# test.net
KiCad netlist of a schematic drawn in EAGLE
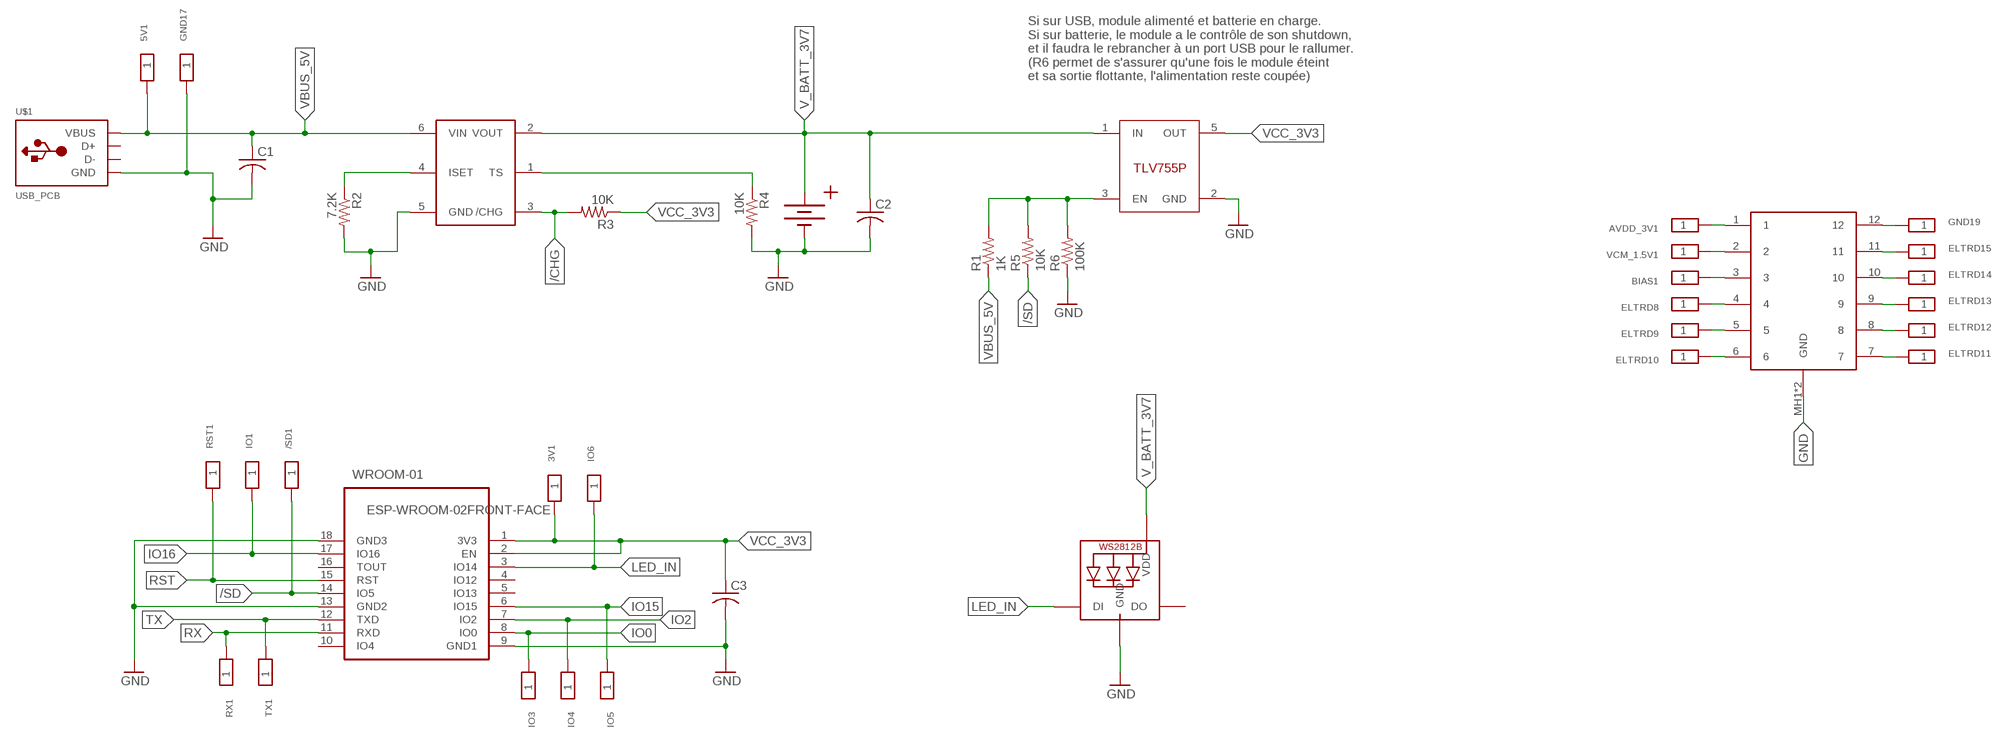
[diagram p0: schematic, sheet 1]

(export (version "E")
  (design (tool "Eeschema 10.0.6"))
  (components
    (comp (ref "/SD1")
      (value "TESTPAD_PROG")
      (footprint "eagle-import:TP1.5MM")
      (libsource (lib "eagle-import") (part "monoblink_wifi_TESTPAD_PROG"))
    )
    (comp (ref "3V1")
      (value "TESTPAD_PROG")
      (footprint "eagle-import:TP1.5MM")
      (libsource (lib "eagle-import") (part "monoblink_wifi_TESTPAD_PROG"))
    )
    (comp (ref "5V1")
      (value "TESTPAD_PROG")
      (footprint "eagle-import:TP1.5MM")
      (libsource (lib "eagle-import") (part "monoblink_wifi_TESTPAD_PROG"))
    )
    (comp (ref "AVDD_3V1")
      (value "TESTPAD_PROG")
      (footprint "eagle-import:TP1.5MM")
      (libsource (lib "eagle-import") (part "TESTPAD_PROG"))
    )
    (comp (ref "BIAS1")
      (value "TESTPAD_PROG")
      (footprint "eagle-import:TP1.5MM")
      (libsource (lib "eagle-import") (part "TESTPAD_PROG"))
    )
    (comp (ref "C1")
      (value "C-USC0603")
      (footprint "eagle-import:C0603")
      (libsource (lib "eagle-import") (part "C-USC0603"))
    )
    (comp (ref "C2")
      (value "C-USC0603")
      (footprint "eagle-import:C0603")
      (libsource (lib "eagle-import") (part "C-USC0603"))
    )
    (comp (ref "C3")
      (value "C-USC0603")
      (footprint "eagle-import:C0603")
      (libsource (lib "eagle-import") (part "C-USC0603"))
    )
    (comp (ref "CHG1")
      (value "BQ21040")
      (footprint "eagle-import:SOT23-6")
      (libsource (lib "eagle-import") (part "BQ21040"))
    )
    (comp (ref "CONN1")
      (value "505110-1292")
      (footprint "eagle-import:505110-1292")
      (libsource (lib "eagle-import") (part "505110-1292"))
    )
    (comp (ref "ELTRD8")
      (value "TESTPAD_PROG")
      (footprint "eagle-import:TP1.5MM")
      (libsource (lib "eagle-import") (part "TESTPAD_PROG"))
    )
    (comp (ref "ELTRD9")
      (value "TESTPAD_PROG")
      (footprint "eagle-import:TP1.5MM")
      (libsource (lib "eagle-import") (part "TESTPAD_PROG"))
    )
    (comp (ref "ELTRD10")
      (value "TESTPAD_PROG")
      (footprint "eagle-import:TP1.5MM")
      (libsource (lib "eagle-import") (part "TESTPAD_PROG"))
    )
    (comp (ref "ELTRD11")
      (value "TESTPAD_PROG")
      (footprint "eagle-import:TP1.5MM")
      (libsource (lib "eagle-import") (part "TESTPAD_PROG"))
    )
    (comp (ref "ELTRD12")
      (value "TESTPAD_PROG")
      (footprint "eagle-import:TP1.5MM")
      (libsource (lib "eagle-import") (part "TESTPAD_PROG"))
    )
    (comp (ref "ELTRD13")
      (value "TESTPAD_PROG")
      (footprint "eagle-import:TP1.5MM")
      (libsource (lib "eagle-import") (part "TESTPAD_PROG"))
    )
    (comp (ref "ELTRD14")
      (value "TESTPAD_PROG")
      (footprint "eagle-import:TP1.5MM")
      (libsource (lib "eagle-import") (part "TESTPAD_PROG"))
    )
    (comp (ref "ELTRD15")
      (value "TESTPAD_PROG")
      (footprint "eagle-import:TP1.5MM")
      (libsource (lib "eagle-import") (part "TESTPAD_PROG"))
    )
    (comp (ref "GND17")
      (value "TESTPAD_PROG")
      (footprint "eagle-import:TP1.5MM")
      (libsource (lib "eagle-import") (part "monoblink_wifi_TESTPAD_PROG"))
    )
    (comp (ref "GND19")
      (value "TESTPAD_PROG")
      (footprint "eagle-import:TP1.5MM")
      (libsource (lib "eagle-import") (part "TESTPAD_PROG"))
    )
    (comp (ref "IO1")
      (value "TESTPAD_PROG")
      (footprint "eagle-import:TP1.5MM")
      (libsource (lib "eagle-import") (part "monoblink_wifi_TESTPAD_PROG"))
    )
    (comp (ref "IO3")
      (value "TESTPAD_PROG")
      (footprint "eagle-import:TP1.5MM")
      (libsource (lib "eagle-import") (part "monoblink_wifi_TESTPAD_PROG"))
    )
    (comp (ref "IO4")
      (value "TESTPAD_PROG")
      (footprint "eagle-import:TP1.5MM")
      (libsource (lib "eagle-import") (part "monoblink_wifi_TESTPAD_PROG"))
    )
    (comp (ref "IO5")
      (value "TESTPAD_PROG")
      (footprint "eagle-import:TP1.5MM")
      (libsource (lib "eagle-import") (part "monoblink_wifi_TESTPAD_PROG"))
    )
    (comp (ref "IO6")
      (value "TESTPAD_PROG")
      (footprint "eagle-import:TP1.5MM")
      (libsource (lib "eagle-import") (part "monoblink_wifi_TESTPAD_PROG"))
    )
    (comp (ref "LDO1")
      (value "TLV755P")
      (footprint "eagle-import:SOT23-5")
      (libsource (lib "eagle-import") (part "TLV755P"))
    )
    (comp (ref "LED1")
      (value "WS2812B5050")
      (footprint "eagle-import:WS2812B")
      (libsource (lib "eagle-import") (part "WS2812B5050"))
    )
    (comp (ref "R1")
      (value "1K")
      (footprint "eagle-import:R0603")
      (libsource (lib "eagle-import") (part "R-US_R0603"))
    )
    (comp (ref "R2")
      (value "7.2K")
      (footprint "eagle-import:R0603")
      (libsource (lib "eagle-import") (part "R-US_R0603"))
    )
    (comp (ref "R3")
      (value "10K")
      (footprint "eagle-import:R0603")
      (libsource (lib "eagle-import") (part "R-US_R0603"))
    )
    (comp (ref "R4")
      (value "10K")
      (footprint "eagle-import:R0603")
      (libsource (lib "eagle-import") (part "R-US_R0603"))
    )
    (comp (ref "R5")
      (value "10K")
      (footprint "eagle-import:R0603")
      (libsource (lib "eagle-import") (part "R-US_R0603"))
    )
    (comp (ref "R6")
      (value "100K")
      (footprint "eagle-import:R0603")
      (libsource (lib "eagle-import") (part "R-US_R0603"))
    )
    (comp (ref "RST1")
      (value "TESTPAD_PROG")
      (footprint "eagle-import:TP1.5MM")
      (libsource (lib "eagle-import") (part "monoblink_wifi_TESTPAD_PROG"))
    )
    (comp (ref "RX1")
      (value "TESTPAD_PROG")
      (footprint "eagle-import:TP1.5MM")
      (libsource (lib "eagle-import") (part "monoblink_wifi_TESTPAD_PROG"))
    )
    (comp (ref "TX1")
      (value "TESTPAD_PROG")
      (footprint "eagle-import:TP1.5MM")
      (libsource (lib "eagle-import") (part "monoblink_wifi_TESTPAD_PROG"))
    )
    (comp (ref "U$1")
      (value "USB_PCB")
      (footprint "eagle-import:USB_PADS")
      (libsource (lib "eagle-import") (part "USB_PCB"))
    )
    (comp (ref "U$3")
      (value "BATT")
      (footprint "eagle-import:BATT_CON")
      (libsource (lib "eagle-import") (part "BATT"))
    )
    (comp (ref "VCM_1.5V1")
      (value "TESTPAD_PROG")
      (footprint "eagle-import:TP1.5MM")
      (libsource (lib "eagle-import") (part "TESTPAD_PROG"))
    )
    (comp (ref "WROOM-01")
      (value "ESP-WROOM-02FRONT-FACE")
      (footprint "eagle-import:FRONT-FACE")
      (libsource (lib "eagle-import") (part "ESP-WROOM-02FRONT-FACE"))
    )
  )
  (nets
    (net (code "1") (name "GND") (class "Default")
      (node (ref "C1") (pin "2") (pinfunction "2_2") (pintype "passive"))
      (node (ref "C2") (pin "2") (pinfunction "2_2") (pintype "passive"))
      (node (ref "C3") (pin "2") (pinfunction "2_2") (pintype "passive"))
      (node (ref "CHG1") (pin "5") (pinfunction "GND_5") (pintype "bidirectional"))
      (node (ref "CONN1") (pin "MH1") (pinfunction "GND_MH1") (pintype "bidirectional"))
      (node (ref "CONN1") (pin "MH2") (pinfunction "GND_MH2") (pintype "bidirectional"))
      (node (ref "GND17") (pin "1") (pinfunction "1_1") (pintype "bidirectional"))
      (node (ref "LDO1") (pin "2") (pinfunction "GND_2") (pintype "bidirectional"))
      (node (ref "LED1") (pin "3-GND") (pinfunction "GND_3-GND") (pintype "power_in"))
      (node (ref "R2") (pin "2") (pinfunction "2_2") (pintype "passive"))
      (node (ref "R4") (pin "2") (pinfunction "2_2") (pintype "passive"))
      (node (ref "R6") (pin "1") (pinfunction "1_1") (pintype "passive"))
      (node (ref "U$1") (pin "GND") (pinfunction "GND_GND") (pintype "power_in"))
      (node (ref "U$3") (pin "V-") (pinfunction "-_V-") (pintype "power_in"))
      (node (ref "WROOM-01") (pin "13") (pinfunction "GND2_13") (pintype "power_in"))
      (node (ref "WROOM-01") (pin "18") (pinfunction "GND3_18") (pintype "power_in"))
      (node (ref "WROOM-01") (pin "9") (pinfunction "GND1_9") (pintype "power_in"))
    )
    (net (code "2") (name "IO0") (class "Default")
      (node (ref "IO3") (pin "1") (pinfunction "1_1") (pintype "bidirectional"))
      (node (ref "WROOM-01") (pin "8") (pinfunction "IO0_8") (pintype "bidirectional"))
    )
    (net (code "3") (name "IO2") (class "Default")
      (node (ref "IO4") (pin "1") (pinfunction "1_1") (pintype "bidirectional"))
      (node (ref "WROOM-01") (pin "7") (pinfunction "IO2_7") (pintype "bidirectional"))
    )
    (net (code "4") (name "IO15") (class "Default")
      (node (ref "IO5") (pin "1") (pinfunction "1_1") (pintype "bidirectional"))
      (node (ref "WROOM-01") (pin "6") (pinfunction "IO15_6") (pintype "bidirectional"))
    )
    (net (code "5") (name "IO16") (class "Default")
      (node (ref "IO1") (pin "1") (pinfunction "1_1") (pintype "bidirectional"))
      (node (ref "WROOM-01") (pin "17") (pinfunction "IO16_17") (pintype "bidirectional"))
    )
    (net (code "6") (name "LED_IN") (class "Default")
      (node (ref "IO6") (pin "1") (pinfunction "1_1") (pintype "bidirectional"))
      (node (ref "LED1") (pin "4-DIN") (pinfunction "DI_4-DIN") (pintype "input"))
      (node (ref "WROOM-01") (pin "3") (pinfunction "IO14_3") (pintype "bidirectional"))
    )
    (net (code "7") (name "Net-(AVDD_3V1-Pad1)") (class "Default")
      (node (ref "AVDD_3V1") (pin "1") (pinfunction "1_1") (pintype "bidirectional"))
      (node (ref "CONN1") (pin "1") (pinfunction "1_1") (pintype "bidirectional"))
    )
    (net (code "8") (name "Net-(BIAS1-Pad1)") (class "Default")
      (node (ref "BIAS1") (pin "1") (pinfunction "1_1") (pintype "bidirectional"))
      (node (ref "CONN1") (pin "3") (pinfunction "3_3") (pintype "bidirectional"))
    )
    (net (code "9") (name "Net-(CHG1-ISET)") (class "Default")
      (node (ref "CHG1") (pin "4") (pinfunction "ISET_4") (pintype "bidirectional"))
      (node (ref "R2") (pin "1") (pinfunction "1_1") (pintype "passive"))
    )
    (net (code "10") (name "Net-(CHG1-TS)") (class "Default")
      (node (ref "CHG1") (pin "1") (pinfunction "TS_1") (pintype "bidirectional"))
      (node (ref "R4") (pin "1") (pinfunction "1_1") (pintype "passive"))
    )
    (net (code "11") (name "Net-(CONN1-Pad2)") (class "Default")
      (node (ref "CONN1") (pin "2") (pinfunction "2_2") (pintype "bidirectional"))
      (node (ref "VCM_1.5V1") (pin "1") (pinfunction "1_1") (pintype "bidirectional"))
    )
    (net (code "12") (name "Net-(CONN1-Pad4)") (class "Default")
      (node (ref "CONN1") (pin "4") (pinfunction "4_4") (pintype "bidirectional"))
      (node (ref "ELTRD8") (pin "1") (pinfunction "1_1") (pintype "bidirectional"))
    )
    (net (code "13") (name "Net-(CONN1-Pad5)") (class "Default")
      (node (ref "CONN1") (pin "5") (pinfunction "5_5") (pintype "bidirectional"))
      (node (ref "ELTRD9") (pin "1") (pinfunction "1_1") (pintype "bidirectional"))
    )
    (net (code "14") (name "Net-(CONN1-Pad6)") (class "Default")
      (node (ref "CONN1") (pin "6") (pinfunction "6_6") (pintype "bidirectional"))
      (node (ref "ELTRD10") (pin "1") (pinfunction "1_1") (pintype "bidirectional"))
    )
    (net (code "15") (name "Net-(CONN1-Pad7)") (class "Default")
      (node (ref "CONN1") (pin "7") (pinfunction "7_7") (pintype "bidirectional"))
      (node (ref "ELTRD11") (pin "1") (pinfunction "1_1") (pintype "bidirectional"))
    )
    (net (code "16") (name "Net-(CONN1-Pad8)") (class "Default")
      (node (ref "CONN1") (pin "8") (pinfunction "8_8") (pintype "bidirectional"))
      (node (ref "ELTRD12") (pin "1") (pinfunction "1_1") (pintype "bidirectional"))
    )
    (net (code "17") (name "Net-(CONN1-Pad9)") (class "Default")
      (node (ref "CONN1") (pin "9") (pinfunction "9_9") (pintype "bidirectional"))
      (node (ref "ELTRD13") (pin "1") (pinfunction "1_1") (pintype "bidirectional"))
    )
    (net (code "18") (name "Net-(CONN1-Pad10)") (class "Default")
      (node (ref "CONN1") (pin "10") (pinfunction "10_10") (pintype "bidirectional"))
      (node (ref "ELTRD14") (pin "1") (pinfunction "1_1") (pintype "bidirectional"))
    )
    (net (code "19") (name "Net-(CONN1-Pad11)") (class "Default")
      (node (ref "CONN1") (pin "11") (pinfunction "11_11") (pintype "bidirectional"))
      (node (ref "ELTRD15") (pin "1") (pinfunction "1_1") (pintype "bidirectional"))
    )
    (net (code "20") (name "Net-(CONN1-Pad12)") (class "Default")
      (node (ref "CONN1") (pin "12") (pinfunction "12_12") (pintype "bidirectional"))
      (node (ref "GND19") (pin "1") (pinfunction "1_1") (pintype "bidirectional"))
    )
    (net (code "21") (name "Net-(LDO1-EN)") (class "Default")
      (node (ref "LDO1") (pin "3") (pinfunction "EN_3") (pintype "bidirectional"))
      (node (ref "R1") (pin "2") (pinfunction "2_2") (pintype "passive"))
      (node (ref "R5") (pin "2") (pinfunction "2_2") (pintype "passive"))
      (node (ref "R6") (pin "2") (pinfunction "2_2") (pintype "passive"))
    )
    (net (code "22") (name "RST") (class "Default")
      (node (ref "RST1") (pin "1") (pinfunction "1_1") (pintype "bidirectional"))
      (node (ref "WROOM-01") (pin "15") (pinfunction "RST_15") (pintype "bidirectional"))
    )
    (net (code "23") (name "RX") (class "Default")
      (node (ref "RX1") (pin "1") (pinfunction "1_1") (pintype "bidirectional"))
      (node (ref "WROOM-01") (pin "11") (pinfunction "RXD_11") (pintype "bidirectional"))
    )
    (net (code "24") (name "TX") (class "Default")
      (node (ref "TX1") (pin "1") (pinfunction "1_1") (pintype "bidirectional"))
      (node (ref "WROOM-01") (pin "12") (pinfunction "TXD_12") (pintype "bidirectional"))
    )
    (net (code "25") (name "VBUS_5V") (class "Default")
      (node (ref "5V1") (pin "1") (pinfunction "1_1") (pintype "bidirectional"))
      (node (ref "C1") (pin "1") (pinfunction "1_1") (pintype "passive"))
      (node (ref "CHG1") (pin "6") (pinfunction "VIN_6") (pintype "bidirectional"))
      (node (ref "R1") (pin "1") (pinfunction "1_1") (pintype "passive"))
      (node (ref "U$1") (pin "V_SUPPLY") (pinfunction "VBUS_V_SUPPLY") (pintype "power_in"))
    )
    (net (code "26") (name "VCC_3V3") (class "Default")
      (node (ref "3V1") (pin "1") (pinfunction "1_1") (pintype "bidirectional"))
      (node (ref "C3") (pin "1") (pinfunction "1_1") (pintype "passive"))
      (node (ref "LDO1") (pin "5") (pinfunction "OUT_5") (pintype "bidirectional"))
      (node (ref "R3") (pin "1") (pinfunction "1_1") (pintype "passive"))
      (node (ref "WROOM-01") (pin "1") (pinfunction "3V3_1") (pintype "power_in"))
      (node (ref "WROOM-01") (pin "2") (pinfunction "EN_2") (pintype "bidirectional"))
    )
    (net (code "27") (name "V_BATT_3V7") (class "Default")
      (node (ref "C2") (pin "1") (pinfunction "1_1") (pintype "passive"))
      (node (ref "CHG1") (pin "2") (pinfunction "VOUT_2") (pintype "bidirectional"))
      (node (ref "LDO1") (pin "1") (pinfunction "IN_1") (pintype "bidirectional"))
      (node (ref "LED1") (pin "1-VDD") (pinfunction "VDD_1-VDD") (pintype "power_in"))
      (node (ref "U$3") (pin "V+") (pinfunction "+_V+") (pintype "power_in"))
    )
    (net (code "28") (name "unconnected-(LED1-DO-Pad2-DOUT)") (class "Default")
      (node (ref "LED1") (pin "2-DOUT") (pinfunction "DO_2-DOUT") (pintype "output"))
    )
    (net (code "29") (name "unconnected-(U$1-PadD+)") (class "Default")
      (node (ref "U$1") (pin "D+") (pinfunction "D+_D+") (pintype "bidirectional"))
    )
    (net (code "30") (name "unconnected-(U$1-PadD-)") (class "Default")
      (node (ref "U$1") (pin "D-") (pinfunction "D-_D-") (pintype "bidirectional"))
    )
    (net (code "31") (name "unconnected-(WROOM-01-IO4-Pad10)") (class "Default")
      (node (ref "WROOM-01") (pin "10") (pinfunction "IO4_10") (pintype "bidirectional"))
    )
    (net (code "32") (name "unconnected-(WROOM-01-IO12-Pad4)") (class "Default")
      (node (ref "WROOM-01") (pin "4") (pinfunction "IO12_4") (pintype "bidirectional"))
    )
    (net (code "33") (name "unconnected-(WROOM-01-IO13-Pad5)") (class "Default")
      (node (ref "WROOM-01") (pin "5") (pinfunction "IO13_5") (pintype "bidirectional"))
    )
    (net (code "34") (name "unconnected-(WROOM-01-TOUT-Pad16)") (class "Default")
      (node (ref "WROOM-01") (pin "16") (pinfunction "TOUT_16") (pintype "bidirectional"))
    )
    (net (code "35") (name "{slash}CHG") (class "Default")
      (node (ref "CHG1") (pin "3") (pinfunction "/CHG_3") (pintype "bidirectional"))
      (node (ref "R3") (pin "2") (pinfunction "2_2") (pintype "passive"))
    )
    (net (code "36") (name "{slash}SD") (class "Default")
      (node (ref "/SD1") (pin "1") (pinfunction "1_1") (pintype "bidirectional"))
      (node (ref "R5") (pin "1") (pinfunction "1_1") (pintype "passive"))
      (node (ref "WROOM-01") (pin "14") (pinfunction "IO5_14") (pintype "open_collector"))
    )
  )
)
